# Power_Decap.net
KiCad netlist of a schematic drawn in Altium Designer
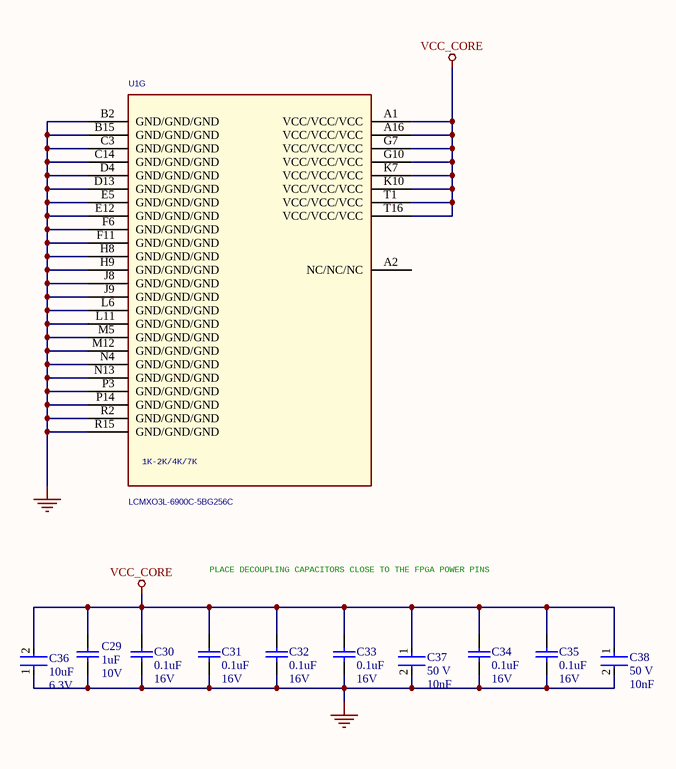
[diagram p0: Power_Decap.SchDoc]

(export (version "E")
  (design (tool "Eeschema 10.0.6"))
  (components
    (comp (ref "C29")
      (value "1uF")
      (footprint "CAPC1608X90X35ML15T15")
      (fields
        (field (name "MANUFACTURER") "Kemet")
        (field (name "PART NUMBER") "C0603C105K8RACTU")
        (field (name "VOLTAGE") "10V")
      )
      (libsource (lib "Altium Content Vault") (part "CAP"))
    )
    (comp (ref "C30")
      (value "0.1uF")
      (footprint "CAPC1608X87X35ML15T15")
      (description "Ceramic Capacitor 0.1uF 16V +-10% X7R0603")
      (fields
        (field (name "PART NUMBER") "C0603C104M4RACTU")
        (field (name "MANUFACTURER") "Kemet")
        (field (name "VOLTAGE") "16V")
      )
      (libsource (lib "Altium Content Vault") (part "CAP"))
    )
    (comp (ref "C31")
      (value "0.1uF")
      (footprint "CAPC1608X87X35ML15T15")
      (description "Ceramic Capacitor 0.1uF 16V +-10% X7R0603")
      (fields
        (field (name "PART NUMBER") "C0603C104M4RACTU")
        (field (name "MANUFACTURER") "Kemet")
        (field (name "VOLTAGE") "16V")
      )
      (libsource (lib "Altium Content Vault") (part "CAP"))
    )
    (comp (ref "C32")
      (value "0.1uF")
      (footprint "CAPC1608X87X35ML15T15")
      (description "Ceramic Capacitor 0.1uF 16V +-10% X7R0603")
      (fields
        (field (name "PART NUMBER") "C0603C104M4RACTU")
        (field (name "MANUFACTURER") "Kemet")
        (field (name "VOLTAGE") "16V")
      )
      (libsource (lib "Altium Content Vault") (part "CAP"))
    )
    (comp (ref "C33")
      (value "0.1uF")
      (footprint "CAPC1608X87X35ML15T15")
      (description "Ceramic Capacitor 0.1uF 16V +-10% X7R0603")
      (fields
        (field (name "PART NUMBER") "C0603C104M4RACTU")
        (field (name "MANUFACTURER") "Kemet")
        (field (name "VOLTAGE") "16V")
      )
      (libsource (lib "Altium Content Vault") (part "CAP"))
    )
    (comp (ref "C34")
      (value "0.1uF")
      (footprint "CAPC1608X87X35ML15T15")
      (description "Ceramic Capacitor 0.1uF 16V +-10% X7R0603")
      (fields
        (field (name "PART NUMBER") "C0603C104M4RACTU")
        (field (name "MANUFACTURER") "Kemet")
        (field (name "VOLTAGE") "16V")
      )
      (libsource (lib "Altium Content Vault") (part "CAP"))
    )
    (comp (ref "C35")
      (value "0.1uF")
      (footprint "CAPC1608X87X35ML15T15")
      (description "Ceramic Capacitor 0.1uF 16V +-10% X7R0603")
      (fields
        (field (name "PART NUMBER") "C0603C104M4RACTU")
        (field (name "MANUFACTURER") "Kemet")
        (field (name "VOLTAGE") "16V")
      )
      (libsource (lib "Altium Content Vault") (part "CAP"))
    )
    (comp (ref "C36")
      (value "10uF")
      (footprint "FP-CL10-IPC_C")
      (description "Cap Ceramic 10uF 6.3V X5R ±20% Pad SMD 0603 +85°C T/R")
      (fields
        (field (name "VOLTAGE") "6.3V")
        (field (name "TOLERANCE") "20%")
        (field (name "MANUFACTURER") "Samsung")
      )
      (libsource (lib "Altium Content Vault") (part "b4654b650e69147ec39a6b967a45e02"))
    )
    (comp (ref "C37")
      (value "10nF")
      (footprint "FP-C0805C-DN-MFG")
      (description "CAP CER 10000PF 50V X7R 0805")
      (fields
        (field (name "VOLTAGE") "50 V")
        (field (name "PART NUMBER") "C0805C103K5RACAUTO")
        (field (name "MANUFACTURER") "KEMET")
      )
      (libsource (lib "Altium Content Vault") (part "b4654b650e69147ec39a6b967a45e02"))
    )
    (comp (ref "C38")
      (value "10nF")
      (footprint "FP-C0805C-DN-MFG")
      (description "CAP CER 10000PF 50V X7R 0805")
      (fields
        (field (name "VOLTAGE") "50 V")
        (field (name "PART NUMBER") "C0805C103K5RACAUTO")
        (field (name "MANUFACTURER") "KEMET")
      )
      (libsource (lib "Altium Content Vault") (part "b4654b650e69147ec39a6b967a45e02"))
    )
    (comp (ref "U1")
      (value "LCMXO3L-6900C-5BG256C")
      (footprint "BGA256C80P16X16_1400X1400X170")
      (description "IC FPGA 6864LUTS 256BGA")
      (fields (field (name "MANUFACTURER") "Lattice semi"))
      (libsource (lib "*") (part "LCMXO3L-1K/2K/4K/7K-BG256"))
    )
  )
  (nets
    (net (code "1") (name "GND") (class "Default")
      (node (ref "C29") (pin "1") (pinfunction "1_1") (pintype "passive"))
      (node (ref "C30") (pin "2") (pinfunction "2_2") (pintype "passive"))
      (node (ref "C31") (pin "2") (pinfunction "2_2") (pintype "passive"))
      (node (ref "C32") (pin "2") (pinfunction "2_2") (pintype "passive"))
      (node (ref "C33") (pin "2") (pinfunction "2_2") (pintype "passive"))
      (node (ref "C34") (pin "2") (pinfunction "2_2") (pintype "passive"))
      (node (ref "C35") (pin "2") (pinfunction "2_2") (pintype "passive"))
      (node (ref "C36") (pin "1") (pinfunction "1_1") (pintype "passive"))
      (node (ref "C37") (pin "2") (pinfunction "2_2") (pintype "passive"))
      (node (ref "C38") (pin "2") (pinfunction "2_2") (pintype "passive"))
      (node (ref "U1") (pin "B15") (pinfunction "GND/GND/GND_B15") (pintype "power_in"))
      (node (ref "U1") (pin "B2") (pinfunction "GND/GND/GND_B2") (pintype "power_in"))
      (node (ref "U1") (pin "C14") (pinfunction "GND/GND/GND_C14") (pintype "power_in"))
      (node (ref "U1") (pin "C3") (pinfunction "GND/GND/GND_C3") (pintype "power_in"))
      (node (ref "U1") (pin "D13") (pinfunction "GND/GND/GND_D13") (pintype "power_in"))
      (node (ref "U1") (pin "D4") (pinfunction "GND/GND/GND_D4") (pintype "power_in"))
      (node (ref "U1") (pin "E12") (pinfunction "GND/GND/GND_E12") (pintype "power_in"))
      (node (ref "U1") (pin "E5") (pinfunction "GND/GND/GND_E5") (pintype "power_in"))
      (node (ref "U1") (pin "F11") (pinfunction "GND/GND/GND_F11") (pintype "power_in"))
      (node (ref "U1") (pin "F6") (pinfunction "GND/GND/GND_F6") (pintype "power_in"))
      (node (ref "U1") (pin "H8") (pinfunction "GND/GND/GND_H8") (pintype "power_in"))
      (node (ref "U1") (pin "H9") (pinfunction "GND/GND/GND_H9") (pintype "power_in"))
      (node (ref "U1") (pin "J8") (pinfunction "GND/GND/GND_J8") (pintype "power_in"))
      (node (ref "U1") (pin "J9") (pinfunction "GND/GND/GND_J9") (pintype "power_in"))
      (node (ref "U1") (pin "L11") (pinfunction "GND/GND/GND_L11") (pintype "power_in"))
      (node (ref "U1") (pin "L6") (pinfunction "GND/GND/GND_L6") (pintype "power_in"))
      (node (ref "U1") (pin "M12") (pinfunction "GND/GND/GND_M12") (pintype "power_in"))
      (node (ref "U1") (pin "M5") (pinfunction "GND/GND/GND_M5") (pintype "power_in"))
      (node (ref "U1") (pin "N13") (pinfunction "GND/GND/GND_N13") (pintype "power_in"))
      (node (ref "U1") (pin "N4") (pinfunction "GND/GND/GND_N4") (pintype "power_in"))
      (node (ref "U1") (pin "P14") (pinfunction "GND/GND/GND_P14") (pintype "power_in"))
      (node (ref "U1") (pin "P3") (pinfunction "GND/GND/GND_P3") (pintype "power_in"))
      (node (ref "U1") (pin "R15") (pinfunction "GND/GND/GND_R15") (pintype "power_in"))
      (node (ref "U1") (pin "R2") (pinfunction "GND/GND/GND_R2") (pintype "power_in"))
    )
    (net (code "2") (name "VCC_CORE") (class "Default")
      (node (ref "C29") (pin "2") (pinfunction "2_2") (pintype "passive"))
      (node (ref "C30") (pin "1") (pinfunction "1_1") (pintype "passive"))
      (node (ref "C31") (pin "1") (pinfunction "1_1") (pintype "passive"))
      (node (ref "C32") (pin "1") (pinfunction "1_1") (pintype "passive"))
      (node (ref "C33") (pin "1") (pinfunction "1_1") (pintype "passive"))
      (node (ref "C34") (pin "1") (pinfunction "1_1") (pintype "passive"))
      (node (ref "C35") (pin "1") (pinfunction "1_1") (pintype "passive"))
      (node (ref "C36") (pin "2") (pinfunction "2_2") (pintype "passive"))
      (node (ref "C37") (pin "1") (pinfunction "1_1") (pintype "passive"))
      (node (ref "C38") (pin "1") (pinfunction "1_1") (pintype "passive"))
      (node (ref "U1") (pin "A1") (pinfunction "VCC/VCC/VCC_A1") (pintype "power_in"))
      (node (ref "U1") (pin "A16") (pinfunction "VCC/VCC/VCC_A16") (pintype "power_in"))
      (node (ref "U1") (pin "G10") (pinfunction "VCC/VCC/VCC_G10") (pintype "power_in"))
      (node (ref "U1") (pin "G7") (pinfunction "VCC/VCC/VCC_G7") (pintype "power_in"))
      (node (ref "U1") (pin "K10") (pinfunction "VCC/VCC/VCC_K10") (pintype "power_in"))
      (node (ref "U1") (pin "K7") (pinfunction "VCC/VCC/VCC_K7") (pintype "power_in"))
      (node (ref "U1") (pin "T1") (pinfunction "VCC/VCC/VCC_T1") (pintype "power_in"))
      (node (ref "U1") (pin "T16") (pinfunction "VCC/VCC/VCC_T16") (pintype "power_in"))
    )
    (net (code "3") (name "unconnected-(U1G-NC{slash}NC{slash}NC-PadA2)") (class "Default")
      (node (ref "U1") (pin "A2") (pinfunction "NC/NC/NC_A2") (pintype "passive"))
    )
  )
)
